# C_lula_4.net
KiCad netlist of a schematic drawn in Altium Designer
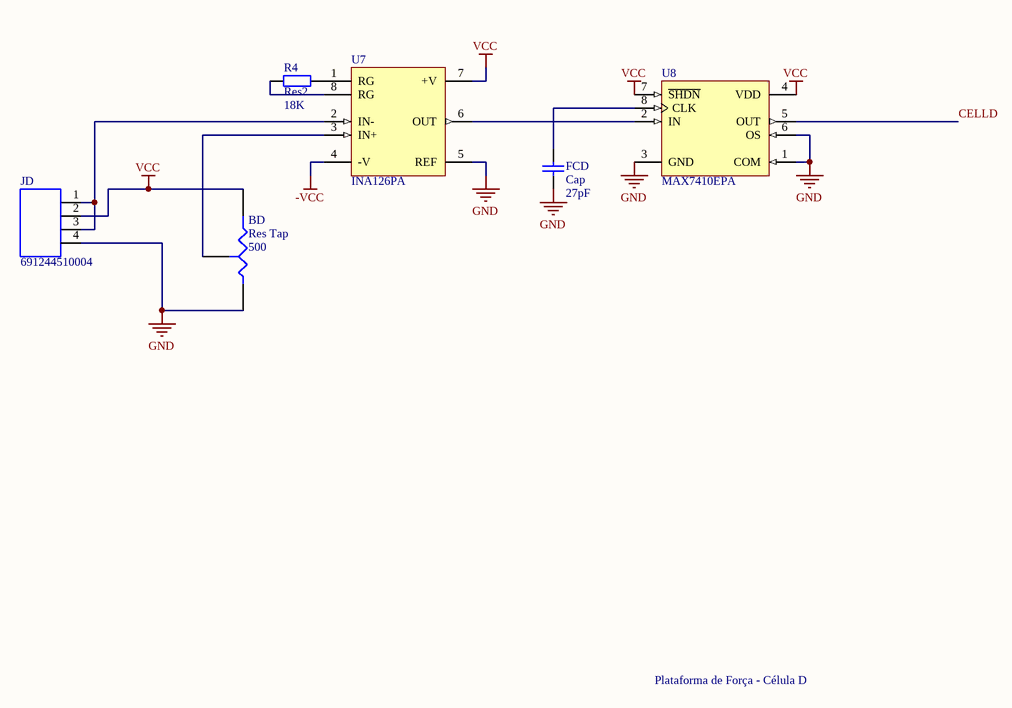
[diagram p0: Célula 4.SchDoc]

(export (version "E")
  (design (tool "Eeschema 10.0.6"))
  (components
    (comp (ref "BD")
      (value "Res Tap")
      (footprint "PcbLib1:TSR3006")
      (description "Tapped Resistor")
      (fields (field (name "ALTIUM_VALUE") "500") (field (name "PUBLISHER") "Altium Limited"))
      (libsource (lib "Miscellaneous Devices") (part "Res Tap"))
    )
    (comp (ref "FCD")
      (value "Cap")
      (footprint "RAD-0.3")
      (description "Capacitor")
      (fields (field (name "ALTIUM_VALUE") "27pF") (field (name "PUBLISHER") "Altium Limited"))
      (libsource (lib "Miscellaneous Devices") (part "Cap"))
    )
    (comp (ref "JD")
      (value "691244510004")
      (footprint "691244510004")
      (description "WR-TBL Horizontal Cable Entry With Rising Cage Clamp,Serie 2445 - 5.08 mm")
      (fields (field (name "MANUFACTURER") "Wurth Elektronik") (field (name "CREATED BY") "Baojun Chen"))
      (libsource (lib "WE_WR-TBL_Rising Cage System_5.08 mm_rev15b") (part "691244510004"))
    )
    (comp (ref "R4")
      (value "Res2")
      (footprint "AXIAL-0.4")
      (description "Resistor")
      (fields (field (name "ALTIUM_VALUE") "18K") (field (name "PUBLISHER") "Altium Limited"))
      (libsource (lib "Miscellaneous Devices") (part "Res2"))
    )
    (comp (ref "U7")
      (value "INA126PA")
      (footprint "006E")
      (description "Precision, Low-Power Instrumentation Amplifiers")
      (fields (field (name "PUBLISHER") "Altium Limited"))
      (libsource (lib "Placa") (part "INA126PA"))
    )
    (comp (ref "U8")
      (value "MAX7410EPA")
      (footprint "PA8")
      (description "5th-Order, Lowpass, Switched-Capacitor Filter")
      (fields (field (name "PUBLISHER") "Altium Limited"))
      (libsource (lib "Maxim Filter Switched Capacitor") (part "MAX7410EPA"))
    )
  )
  (nets
    (net (code "1") (name "-VCC") (class "Default")
      (node (ref "U7") (pin "4") (pinfunction "-V_4") (pintype "power_in"))
    )
    (net (code "2") (name "/CELLD") (class "Default")
      (node (ref "U8") (pin "5") (pinfunction "OUT_5") (pintype "output"))
    )
    (net (code "3") (name "GND") (class "Default")
      (node (ref "BD") (pin "1") (pinfunction "A_1") (pintype "passive"))
      (node (ref "FCD") (pin "1") (pinfunction "1_1") (pintype "passive"))
      (node (ref "JD") (pin "4") (pinfunction "4_4") (pintype "passive"))
      (node (ref "U7") (pin "5") (pinfunction "REF_5") (pintype "passive"))
      (node (ref "U8") (pin "1") (pinfunction "COM_1") (pintype "input"))
      (node (ref "U8") (pin "3") (pinfunction "GND_3") (pintype "power_in"))
      (node (ref "U8") (pin "6") (pinfunction "OS_6") (pintype "input"))
    )
    (net (code "4") (name "Net-(BD-TAP)") (class "Default")
      (node (ref "BD") (pin "3") (pinfunction "TAP_3") (pintype "passive"))
      (node (ref "U7") (pin "3") (pinfunction "IN+_3") (pintype "input"))
    )
    (net (code "5") (name "Net-(R4-Pad1)") (class "Default")
      (node (ref "R4") (pin "1") (pinfunction "1_1") (pintype "passive"))
      (node (ref "U7") (pin "8") (pinfunction "RG_8") (pintype "passive"))
    )
    (net (code "6") (name "Net-(R4-Pad2)") (class "Default")
      (node (ref "R4") (pin "2") (pinfunction "2_2") (pintype "passive"))
      (node (ref "U7") (pin "1") (pinfunction "RG_1") (pintype "passive"))
    )
    (net (code "7") (name "Net-(U7-IN-)") (class "Default")
      (node (ref "JD") (pin "1") (pinfunction "1_1") (pintype "passive"))
      (node (ref "JD") (pin "3") (pinfunction "3_3") (pintype "passive"))
      (node (ref "U7") (pin "2") (pinfunction "IN-_2") (pintype "input"))
    )
    (net (code "8") (name "Net-(U7-OUT)") (class "Default")
      (node (ref "U7") (pin "6") (pinfunction "OUT_6") (pintype "output"))
      (node (ref "U8") (pin "2") (pinfunction "IN_2") (pintype "input"))
    )
    (net (code "9") (name "Net-(U8-CLK)") (class "Default")
      (node (ref "FCD") (pin "2") (pinfunction "2_2") (pintype "passive"))
      (node (ref "U8") (pin "8") (pinfunction "CLK_8") (pintype "input"))
    )
    (net (code "10") (name "VCC") (class "Default")
      (node (ref "BD") (pin "2") (pinfunction "B_2") (pintype "passive"))
      (node (ref "JD") (pin "2") (pinfunction "2_2") (pintype "passive"))
      (node (ref "U7") (pin "7") (pinfunction "+V_7") (pintype "power_in"))
      (node (ref "U8") (pin "4") (pinfunction "VDD_4") (pintype "power_in"))
      (node (ref "U8") (pin "7") (pinfunction "~{SHDN}_7") (pintype "input"))
    )
  )
)
